# converter.net
KiCad netlist of a schematic drawn in EAGLE
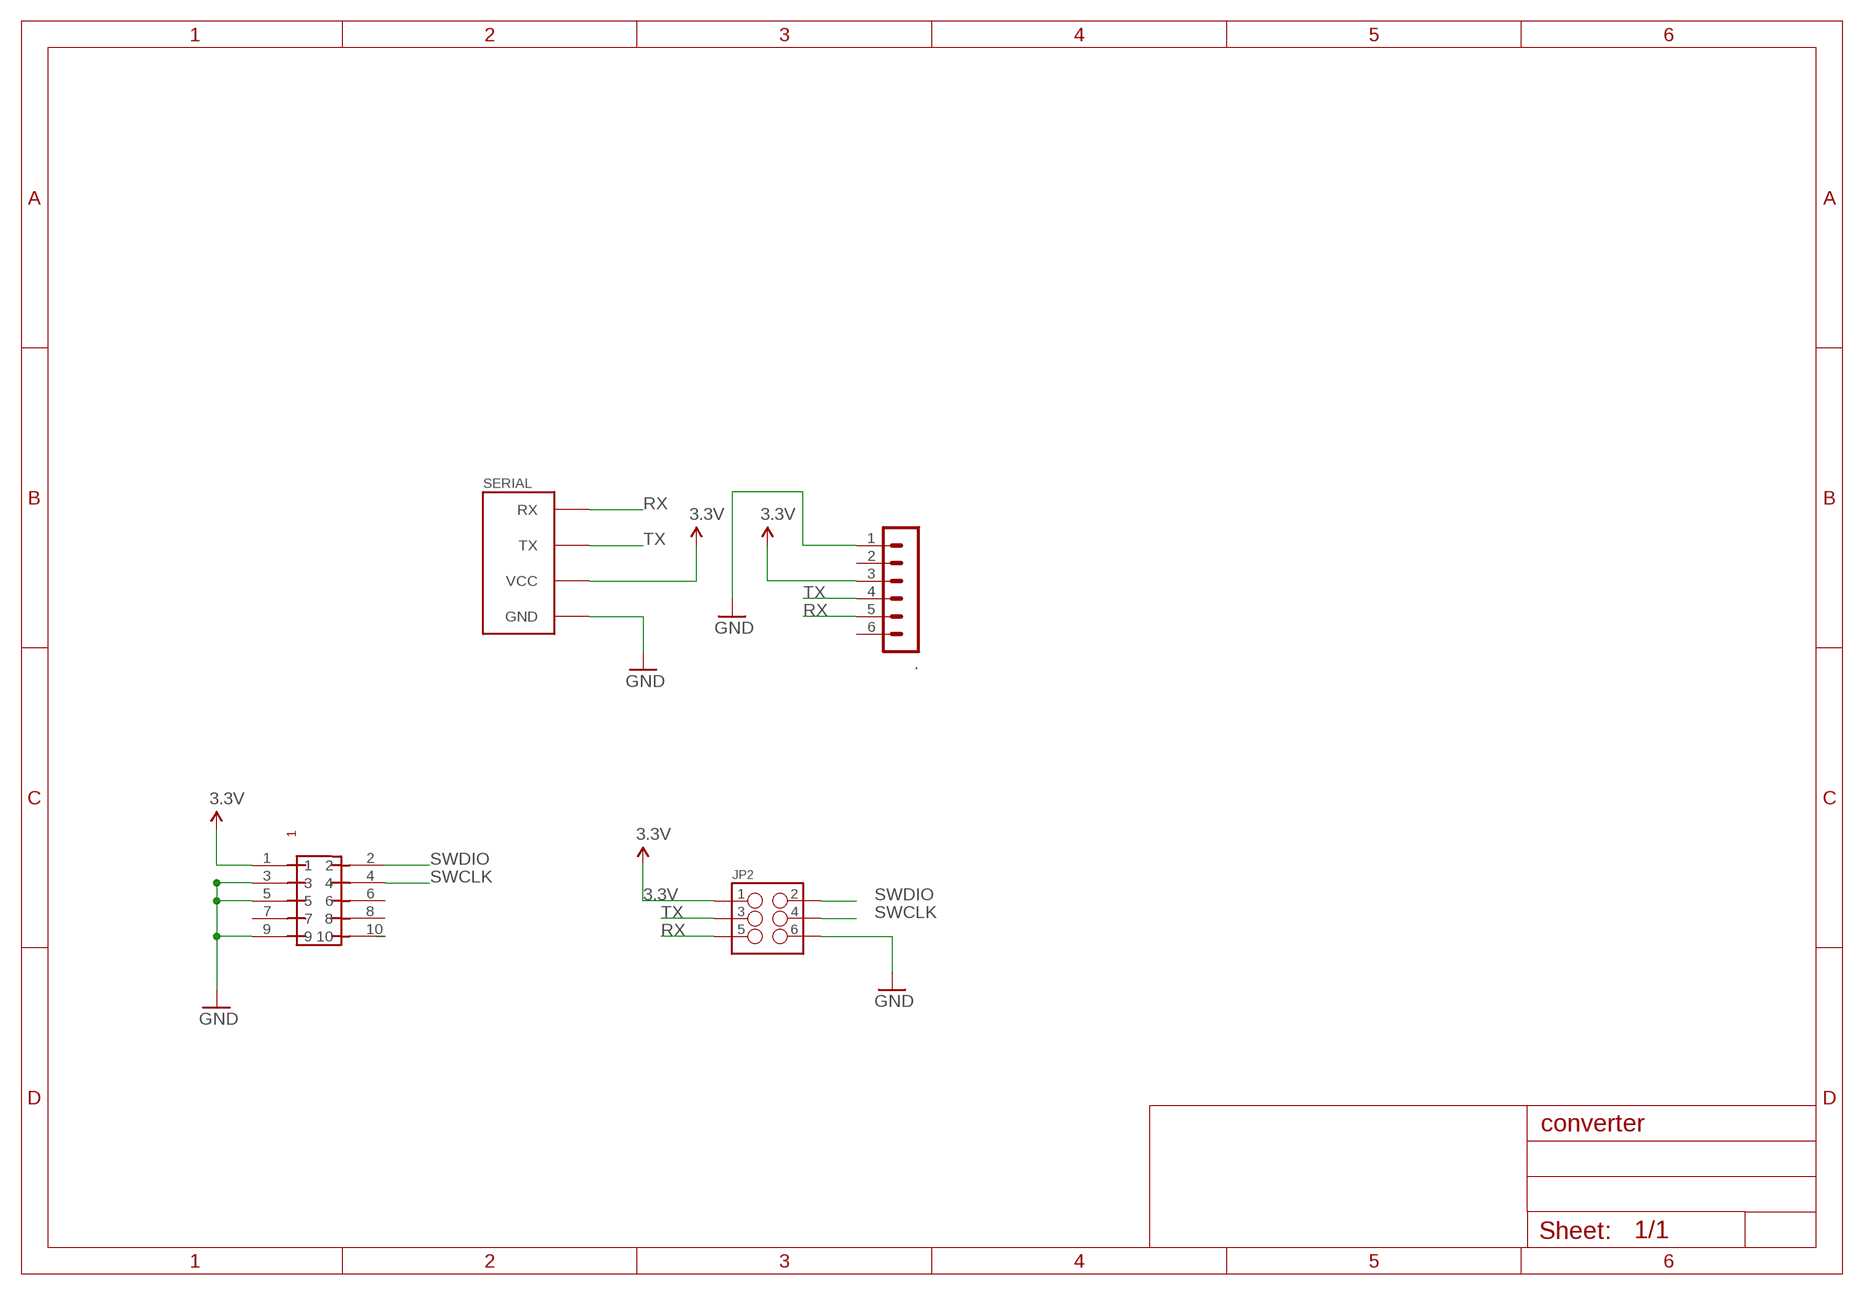
[diagram p0: schematic, sheet 1]

(export (version "E")
  (design (tool "Eeschema 10.0.6"))
  (components
    (comp (ref ".")
      (value "MA06-1")
      (footprint "eagle-import:MA06-1")
      (libsource (lib "eagle-import") (part "MA06-1"))
    )
    (comp (ref "JP2")
      (value "M03X2")
      (footprint "eagle-import:2X3-SHROUDED")
      (libsource (lib "eagle-import") (part "M03X2"))
    )
    (comp (ref "SERIAL")
      (value "FABO_BRICK_SERIAL-CONNECTOR_I")
      (footprint "eagle-import:FABO_BRICK_SERIAL_CONNECTOR_I")
      (libsource (lib "eagle-import") (part "FABO_BRICK_SERIAL-CONNECTOR_I"))
    )
    (comp (ref "U$5")
      (value "PIN-HEADER-SMT(1.27MM)2X5")
      (footprint "eagle-import:PIN-HEADER-SMT(1.27MM)2X5")
      (libsource (lib "eagle-import") (part "PIN-HEADER-SMT(1.27MM)2X5"))
    )
  )
  (nets
    (net (code "1") (name "/RX") (class "Default")
      (node (ref ".") (pin "5") (pinfunction "5_5") (pintype "passive"))
      (node (ref "JP2") (pin "5") (pinfunction "5_5") (pintype "bidirectional"))
      (node (ref "SERIAL") (pin "RX") (pinfunction "RX_RX") (pintype "bidirectional"))
    )
    (net (code "2") (name "/SWCLK") (class "Default")
      (node (ref "JP2") (pin "4") (pinfunction "4_4") (pintype "bidirectional"))
      (node (ref "U$5") (pin "4") (pinfunction "4_4") (pintype "bidirectional"))
    )
    (net (code "3") (name "/SWDIO") (class "Default")
      (node (ref "JP2") (pin "2") (pinfunction "2_2") (pintype "bidirectional"))
      (node (ref "U$5") (pin "2") (pinfunction "2_2") (pintype "bidirectional"))
    )
    (net (code "4") (name "/TX") (class "Default")
      (node (ref ".") (pin "4") (pinfunction "4_4") (pintype "passive"))
      (node (ref "JP2") (pin "3") (pinfunction "3_3") (pintype "bidirectional"))
      (node (ref "SERIAL") (pin "TX") (pinfunction "TX_TX") (pintype "bidirectional"))
    )
    (net (code "5") (name "3.3V") (class "Default")
      (node (ref ".") (pin "3") (pinfunction "3_3") (pintype "passive"))
      (node (ref "JP2") (pin "1") (pinfunction "1_1") (pintype "bidirectional"))
      (node (ref "SERIAL") (pin "VCC") (pinfunction "VCC_VCC") (pintype "bidirectional"))
      (node (ref "U$5") (pin "1") (pinfunction "1_1") (pintype "bidirectional"))
    )
    (net (code "6") (name "GND") (class "Default")
      (node (ref ".") (pin "1") (pinfunction "1_1") (pintype "passive"))
      (node (ref "JP2") (pin "6") (pinfunction "6_6") (pintype "bidirectional"))
      (node (ref "SERIAL") (pin "GND") (pinfunction "GND_GND") (pintype "bidirectional"))
      (node (ref "U$5") (pin "3") (pinfunction "3_3") (pintype "bidirectional"))
      (node (ref "U$5") (pin "5") (pinfunction "5_5") (pintype "bidirectional"))
      (node (ref "U$5") (pin "9") (pinfunction "9_9") (pintype "bidirectional"))
    )
    (net (code "7") (name "unconnected-(.-Pad2)") (class "Default")
      (node (ref ".") (pin "2") (pinfunction "2_2") (pintype "passive"))
    )
    (net (code "8") (name "unconnected-(.-Pad6)") (class "Default")
      (node (ref ".") (pin "6") (pinfunction "6_6") (pintype "passive"))
    )
    (net (code "9") (name "unconnected-(U$5-Pad6)") (class "Default")
      (node (ref "U$5") (pin "6") (pinfunction "6_6") (pintype "bidirectional"))
    )
    (net (code "10") (name "unconnected-(U$5-Pad7)") (class "Default")
      (node (ref "U$5") (pin "7") (pinfunction "7_7") (pintype "bidirectional"))
    )
    (net (code "11") (name "unconnected-(U$5-Pad8)") (class "Default")
      (node (ref "U$5") (pin "8") (pinfunction "8_8") (pintype "bidirectional"))
    )
    (net (code "12") (name "unconnected-(U$5-Pad10)") (class "Default")
      (node (ref "U$5") (pin "10") (pinfunction "10_10") (pintype "bidirectional"))
    )
  )
)
